# Power.net
KiCad netlist of a schematic drawn in Altium Designer
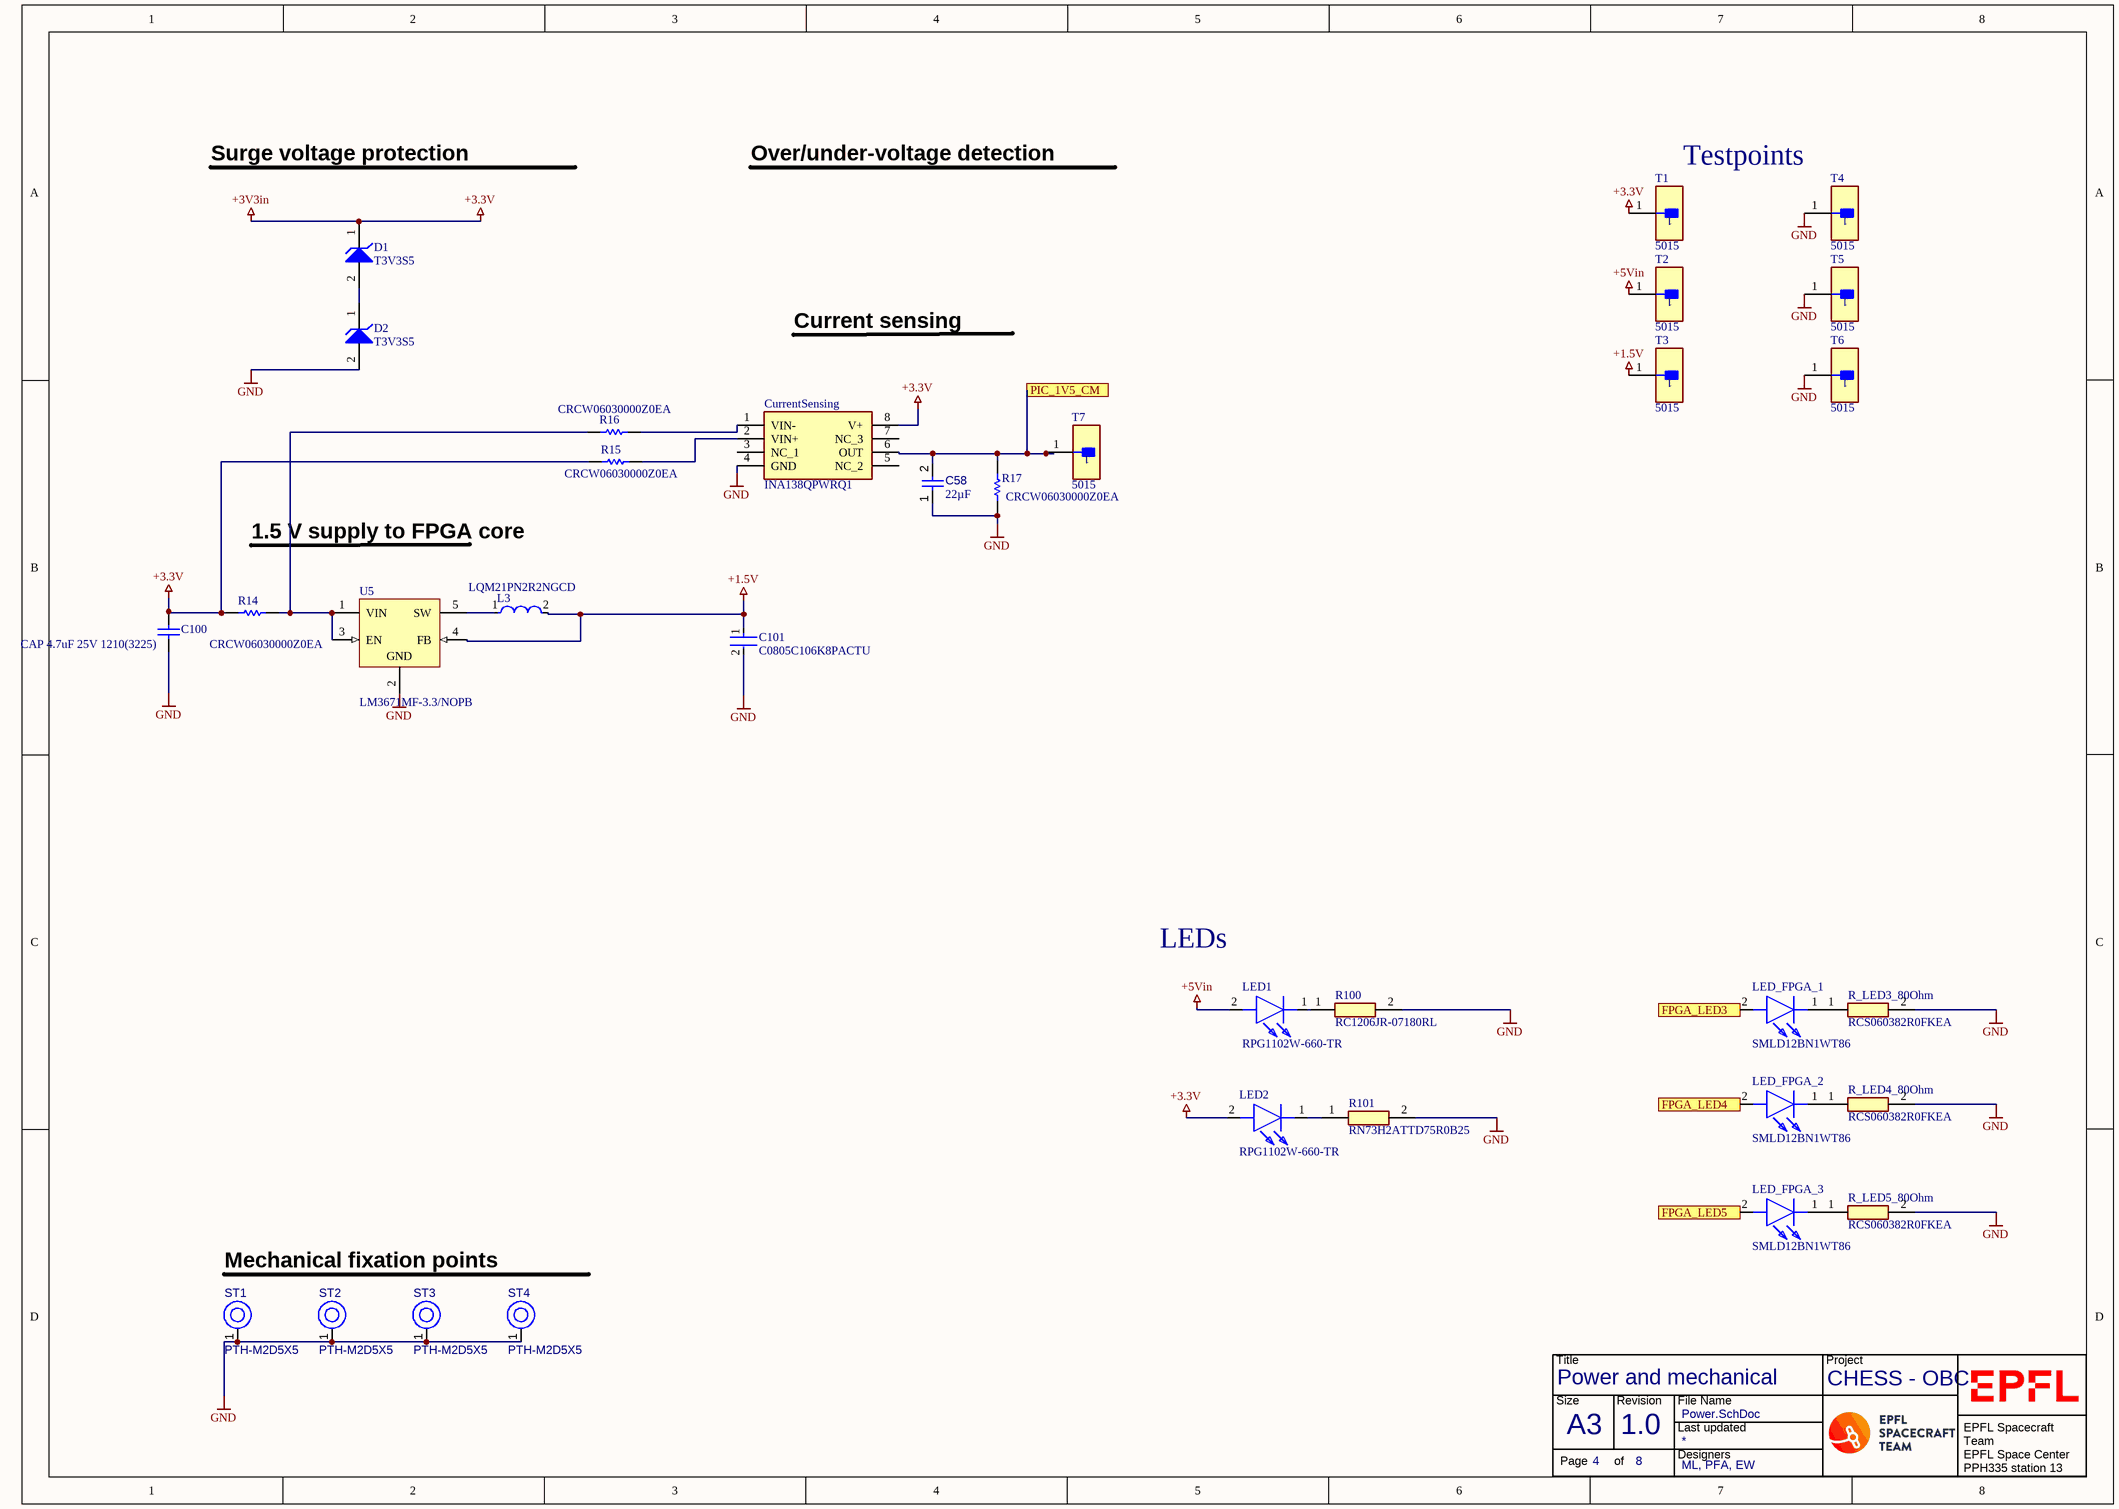
[diagram p0: Power.SchDoc]

(export (version "E")
  (design (tool "Eeschema 10.0.6"))
  (components
    (comp (ref "C58")
      (value "22µF")
      (footprint "CAPC0805(2012)145_L")
      (description "Chip Capacitor, 22µF +/-40%, 16V, 0805, Thickness 1.45 mm")
      (fields (field (name "TOLERANCE") "5%") (field (name "Comment") "Capacitor 22µF +/-40% 16V 0805"))
      (libsource (lib "EPFL") (part "CAP-NP-2"))
    )
    (comp (ref "C100")
      (value "CAP 4.7uF 25V 1210(3225)")
      (footprint "CAPC1210(3225)220_M")
      (description "CAP 4.7uF 25V ±10% 1210 (3225 Metric) Thickness 2.2mm SMD")
      (fields (field (name "TOLERANCE") "Â±10%"))
      (libsource (lib "Altium Content Vault") (part "CAP"))
    )
    (comp (ref "C101")
      (value "C0805C106K8PACTU")
      (footprint "FP-C0805C-DG-MFG")
      (description "CAP CER 10UF 10V X5R 0805")
      (fields (field (name "TOLERANCE") "10%") (field (name "MANUFACTURER") "Kemet"))
      (libsource (lib "Altium Content Vault") (part "11868f565c42a9108669ba33697ecf6"))
    )
    (comp (ref "CurrentSensing")
      (value "INA138QPWRQ1")
      (footprint "SamacSys:SOP65P640X120-8N")
      (description "Integrated Circuit")
      (fields (field (name "MOUSER2 PART NUMBER") "595-INA138QPWRQ1"))
      (libsource (lib "*") (part "INA138QPWRQ1"))
    )
    (comp (ref "D1")
      (value "T3V3S5")
      (footprint "ONSC-SOD-523-2-502-01_V")
      (fields (field (name "MANUFACTURER") "On Semiconductor") (field (name "PARTNUMBER") "ESD5Z7.0T1G"))
      (libsource (lib "Altium Content Vault") (part "ONSC-K1A2-2"))
    )
    (comp (ref "D2")
      (value "T3V3S5")
      (footprint "ONSC-SOD-523-2-502-01_V")
      (fields (field (name "MANUFACTURER") "On Semiconductor") (field (name "PARTNUMBER") "ESD5Z7.0T1G"))
      (libsource (lib "Altium Content Vault") (part "ONSC-K1A2-2"))
    )
    (comp (ref "L3")
      (value "LQM21PN2R2NGCD")
      (footprint "FP-LQM21PH_G0-IPC_C")
      (description "Multilayer Type Inductor for Power Lines, 0805 (2012), 2.2μH, 30%, 0.288Ω, 0.8A")
      (fields (field (name "TOLERANCE") "30%"))
      (libsource (lib "Altium Content Vault") (part "725321dda6339637d4d059423bc1c3c"))
    )
    (comp (ref "LED1")
      (value "RPG1102W-660-TR")
      (footprint "SamacSys:LEDC3015X190N")
      (description "LED")
      (fields (field (name "MOUSER2 PART NUMBER") "327-RPG1102W660TR"))
      (libsource (lib "*") (part "RPG1102W-660-TR"))
    )
    (comp (ref "LED2")
      (value "RPG1102W-660-TR")
      (footprint "SamacSys:LEDC3015X190N")
      (description "LED")
      (fields (field (name "MOUSER2 PART NUMBER") "327-RPG1102W660TR"))
      (libsource (lib "*") (part "RPG1102W-660-TR"))
    )
    (comp (ref "LED_FPGA_1")
      (value "SMLD12BN1WT86")
      (footprint "SamacSys:LEDM168X65N")
      (description "LED")
      (libsource (lib "*") (part "SMLD12BN1WT86"))
    )
    (comp (ref "LED_FPGA_2")
      (value "SMLD12BN1WT86")
      (footprint "SamacSys:LEDM168X65N")
      (description "LED")
      (libsource (lib "*") (part "SMLD12BN1WT86"))
    )
    (comp (ref "LED_FPGA_3")
      (value "SMLD12BN1WT86")
      (footprint "SamacSys:LEDM168X65N")
      (description "LED")
      (libsource (lib "*") (part "SMLD12BN1WT86"))
    )
    (comp (ref "R14")
      (value "CRCW06030000Z0EA")
      (footprint "RESC1609X50X30NL8T20")
      (description "Chip Resistor, 0 Ohm, Jumper, 100 mW, -55 to 155 degC, 0603 (1608 Metric), RoHS, Tape and Reel")
      (fields (field (name "MANUFACTURER") "Vishay Semiconductor"))
      (libsource (lib "Altium Content Vault") (part "RES-2"))
    )
    (comp (ref "R15")
      (value "CRCW06030000Z0EA")
      (footprint "RESC1609X50X30NL8T20")
      (description "Chip Resistor, 0 Ohm, Jumper, 100 mW, -55 to 155 degC, 0603 (1608 Metric), RoHS, Tape and Reel")
      (fields (field (name "MANUFACTURER") "Vishay Semiconductor"))
      (libsource (lib "Altium Content Vault") (part "RES-2"))
    )
    (comp (ref "R16")
      (value "CRCW06030000Z0EA")
      (footprint "RESC1609X50X30NL8T20")
      (description "Chip Resistor, 0 Ohm, Jumper, 100 mW, -55 to 155 degC, 0603 (1608 Metric), RoHS, Tape and Reel")
      (fields (field (name "MANUFACTURER") "Vishay Semiconductor"))
      (libsource (lib "Altium Content Vault") (part "RES-2"))
    )
    (comp (ref "R17")
      (value "CRCW06030000Z0EA")
      (footprint "RESC1609X50X30NL8T20")
      (description "Chip Resistor, 0 Ohm, Jumper, 100 mW, -55 to 155 degC, 0603 (1608 Metric), RoHS, Tape and Reel")
      (fields (field (name "MANUFACTURER") "Vishay Semiconductor"))
      (libsource (lib "Altium Content Vault") (part "RES-2"))
    )
    (comp (ref "R100")
      (value "RC1206JR-07180RL")
      (footprint "SamacSys:RESC3116X65N")
      (description "Resistor")
      (libsource (lib "*") (part "RC1206JR-07180RL"))
    )
    (comp (ref "R101")
      (value "RN73H2ATTD75R0B25")
      (footprint "SamacSys:RESC2012X60N")
      (description "Resistor")
      (libsource (lib "*") (part "RN73H2ATTD75R0B25"))
    )
    (comp (ref "R_LED3_80Ohm")
      (value "RCS060382R0FKEA")
      (footprint "SamacSys:RESC1608X50N")
      (description "Resistor")
      (fields (field (name "MOUSER2 PART NUMBER") "71-RCS060382R0FKEA"))
      (libsource (lib "*") (part "RCS060382R0FKEA"))
    )
    (comp (ref "R_LED4_80Ohm")
      (value "RCS060382R0FKEA")
      (footprint "SamacSys:RESC1608X50N")
      (description "Resistor")
      (fields (field (name "MOUSER2 PART NUMBER") "71-RCS060382R0FKEA"))
      (libsource (lib "*") (part "RCS060382R0FKEA"))
    )
    (comp (ref "R_LED5_80Ohm")
      (value "RCS060382R0FKEA")
      (footprint "SamacSys:RESC1608X50N")
      (description "Resistor")
      (fields (field (name "MOUSER2 PART NUMBER") "71-RCS060382R0FKEA"))
      (libsource (lib "*") (part "RCS060382R0FKEA"))
    )
    (comp (ref "ST1")
      (value "PTH-M2D5X5")
      (footprint "PTH-M2D5X5")
      (description "M2 PTH (2.5mm), 5mm pad")
      (libsource (lib "EPFL") (part "CMP-00028-00000-1"))
    )
    (comp (ref "ST2")
      (value "PTH-M2D5X5")
      (footprint "PTH-M2D5X5")
      (description "M2 PTH (2.5mm), 5mm pad")
      (libsource (lib "EPFL") (part "CMP-00028-00000-1"))
    )
    (comp (ref "ST3")
      (value "PTH-M2D5X5")
      (footprint "PTH-M2D5X5")
      (description "M2 PTH (2.5mm), 5mm pad")
      (libsource (lib "EPFL") (part "CMP-00028-00000-1"))
    )
    (comp (ref "ST4")
      (value "PTH-M2D5X5")
      (footprint "PTH-M2D5X5")
      (description "M2 PTH (2.5mm), 5mm pad")
      (libsource (lib "EPFL") (part "CMP-00028-00000-1"))
    )
    (comp (ref "T1")
      (value "5015")
      (footprint "FP-5015-MFG")
      (description "PC TEST POINT MINIATURE")
      (fields
        (field (name "MANUFACTURER") "keystone")
        (field (name "OCTOPART") "https://octopart.com/5015-keystone-3822")
      )
      (libsource (lib "Altium Content Vault") (part "dd45045ce8184df9e99e12baf3f412c"))
    )
    (comp (ref "T2")
      (value "5015")
      (footprint "FP-5015-MFG")
      (description "PC TEST POINT MINIATURE")
      (fields
        (field (name "MANUFACTURER") "keystone")
        (field (name "OCTOPART") "https://octopart.com/5015-keystone-3822")
      )
      (libsource (lib "Altium Content Vault") (part "dd45045ce8184df9e99e12baf3f412c"))
    )
    (comp (ref "T3")
      (value "5015")
      (footprint "FP-5015-MFG")
      (description "PC TEST POINT MINIATURE")
      (fields
        (field (name "MANUFACTURER") "keystone")
        (field (name "OCTOPART") "https://octopart.com/5015-keystone-3822")
      )
      (libsource (lib "Altium Content Vault") (part "dd45045ce8184df9e99e12baf3f412c"))
    )
    (comp (ref "T4")
      (value "5015")
      (footprint "FP-5015-MFG")
      (description "PC TEST POINT MINIATURE")
      (fields
        (field (name "MANUFACTURER") "keystone")
        (field (name "OCTOPART") "https://octopart.com/5015-keystone-3822")
      )
      (libsource (lib "Altium Content Vault") (part "dd45045ce8184df9e99e12baf3f412c"))
    )
    (comp (ref "T5")
      (value "5015")
      (footprint "FP-5015-MFG")
      (description "PC TEST POINT MINIATURE")
      (fields
        (field (name "MANUFACTURER") "keystone")
        (field (name "OCTOPART") "https://octopart.com/5015-keystone-3822")
      )
      (libsource (lib "Altium Content Vault") (part "dd45045ce8184df9e99e12baf3f412c"))
    )
    (comp (ref "T6")
      (value "5015")
      (footprint "FP-5015-MFG")
      (description "PC TEST POINT MINIATURE")
      (fields
        (field (name "MANUFACTURER") "keystone")
        (field (name "OCTOPART") "https://octopart.com/5015-keystone-3822")
      )
      (libsource (lib "Altium Content Vault") (part "dd45045ce8184df9e99e12baf3f412c"))
    )
    (comp (ref "T7")
      (value "5015")
      (footprint "FP-5015-MFG")
      (description "PC TEST POINT MINIATURE")
      (fields
        (field (name "MANUFACTURER") "keystone")
        (field (name "OCTOPART") "https://octopart.com/5015-keystone-3822")
      )
      (libsource (lib "Altium Content Vault") (part "dd45045ce8184df9e99e12baf3f412c"))
    )
    (comp (ref "U5")
      (value "LM3671MF-3.3/NOPB")
      (footprint "DBV0005A_N")
      (description "2MHz, 600mA Step-Down DC-DC Converter, 5-pin SOT-23, Pb-Free")
      (fields (field (name "MANUFACTURER") "Texas Instruments"))
      (libsource (lib "Altium Content Vault") (part "PM-DCDC-LM3670-5"))
    )
  )
  (nets
    (net (code "1") (name "+1.5V") (class "Default")
      (node (ref "C101") (pin "1") (pinfunction "1_1") (pintype "passive"))
      (node (ref "L3") (pin "2") (pinfunction "2_2") (pintype "passive"))
      (node (ref "T3") (pin "1") (pinfunction "1_1") (pintype "passive"))
      (node (ref "U5") (pin "4") (pinfunction "FB_4") (pintype "input"))
    )
    (net (code "2") (name "+3.3V") (class "Default")
      (node (ref "C100") (pin "2") (pinfunction "2_2") (pintype "passive"))
      (node (ref "CurrentSensing") (pin "8") (pinfunction "V+_8") (pintype "passive"))
      (node (ref "D1") (pin "1") (pinfunction "K_1") (pintype "passive"))
      (node (ref "LED2") (pin "2") (pinfunction "A_2") (pintype "passive"))
      (node (ref "R14") (pin "1") (pinfunction "1_1") (pintype "passive"))
      (node (ref "R15") (pin "1") (pinfunction "1_1") (pintype "passive"))
      (node (ref "T1") (pin "1") (pinfunction "1_1") (pintype "passive"))
    )
    (net (code "3") (name "+5Vin") (class "Default")
      (node (ref "LED1") (pin "2") (pinfunction "A_2") (pintype "passive"))
      (node (ref "T2") (pin "1") (pinfunction "1_1") (pintype "passive"))
    )
    (net (code "4") (name "/FPGA_LED3") (class "Default")
      (node (ref "LED_FPGA_1") (pin "2") (pinfunction "A_2") (pintype "passive"))
    )
    (net (code "5") (name "/FPGA_LED4") (class "Default")
      (node (ref "LED_FPGA_2") (pin "2") (pinfunction "A_2") (pintype "passive"))
    )
    (net (code "6") (name "/FPGA_LED5") (class "Default")
      (node (ref "LED_FPGA_3") (pin "2") (pinfunction "A_2") (pintype "passive"))
    )
    (net (code "7") (name "/PIC_1V5_CM") (class "Default")
      (node (ref "C58") (pin "2") (pinfunction "2_2") (pintype "passive"))
      (node (ref "CurrentSensing") (pin "6") (pinfunction "OUT_6") (pintype "passive"))
      (node (ref "R17") (pin "2") (pinfunction "2_2") (pintype "passive"))
      (node (ref "T7") (pin "1") (pinfunction "1_1") (pintype "passive"))
    )
    (net (code "8") (name "GND") (class "Default")
      (node (ref "C100") (pin "1") (pinfunction "1_1") (pintype "passive"))
      (node (ref "C101") (pin "2") (pinfunction "2_2") (pintype "passive"))
      (node (ref "C58") (pin "1") (pinfunction "1_1") (pintype "passive"))
      (node (ref "CurrentSensing") (pin "4") (pinfunction "GND_4") (pintype "passive"))
      (node (ref "D2") (pin "2") (pinfunction "A_2") (pintype "passive"))
      (node (ref "R100") (pin "2") (pinfunction "2_2") (pintype "passive"))
      (node (ref "R101") (pin "2") (pinfunction "2_2") (pintype "passive"))
      (node (ref "R17") (pin "1") (pinfunction "1_1") (pintype "passive"))
      (node (ref "R_LED3_80Ohm") (pin "2") (pinfunction "2_2") (pintype "passive"))
      (node (ref "R_LED4_80Ohm") (pin "2") (pinfunction "2_2") (pintype "passive"))
      (node (ref "R_LED5_80Ohm") (pin "2") (pinfunction "2_2") (pintype "passive"))
      (node (ref "ST1") (pin "1") (pinfunction "H1_1") (pintype "passive"))
      (node (ref "ST2") (pin "1") (pinfunction "H1_1") (pintype "passive"))
      (node (ref "ST3") (pin "1") (pinfunction "H1_1") (pintype "passive"))
      (node (ref "ST4") (pin "1") (pinfunction "H1_1") (pintype "passive"))
      (node (ref "T4") (pin "1") (pinfunction "1_1") (pintype "passive"))
      (node (ref "T5") (pin "1") (pinfunction "1_1") (pintype "passive"))
      (node (ref "T6") (pin "1") (pinfunction "1_1") (pintype "passive"))
      (node (ref "U5") (pin "2") (pinfunction "GND_2") (pintype "power_in"))
    )
    (net (code "9") (name "Net-(CurrentSensing-VIN+)") (class "Default")
      (node (ref "CurrentSensing") (pin "2") (pinfunction "VIN+_2") (pintype "passive"))
      (node (ref "R15") (pin "2") (pinfunction "2_2") (pintype "passive"))
    )
    (net (code "10") (name "Net-(CurrentSensing-VIN-)") (class "Default")
      (node (ref "CurrentSensing") (pin "1") (pinfunction "VIN-_1") (pintype "passive"))
      (node (ref "R16") (pin "2") (pinfunction "2_2") (pintype "passive"))
    )
    (net (code "11") (name "Net-(D1-A)") (class "Default")
      (node (ref "D1") (pin "2") (pinfunction "A_2") (pintype "passive"))
      (node (ref "D2") (pin "1") (pinfunction "K_1") (pintype "passive"))
    )
    (net (code "12") (name "Net-(LED1-K)") (class "Default")
      (node (ref "LED1") (pin "1") (pinfunction "K_1") (pintype "passive"))
      (node (ref "R100") (pin "1") (pinfunction "1_1") (pintype "passive"))
    )
    (net (code "13") (name "Net-(LED2-K)") (class "Default")
      (node (ref "LED2") (pin "1") (pinfunction "K_1") (pintype "passive"))
      (node (ref "R101") (pin "1") (pinfunction "1_1") (pintype "passive"))
    )
    (net (code "14") (name "Net-(LED_FPGA_1-K)") (class "Default")
      (node (ref "LED_FPGA_1") (pin "1") (pinfunction "K_1") (pintype "passive"))
      (node (ref "R_LED3_80Ohm") (pin "1") (pinfunction "1_1") (pintype "passive"))
    )
    (net (code "15") (name "Net-(LED_FPGA_2-K)") (class "Default")
      (node (ref "LED_FPGA_2") (pin "1") (pinfunction "K_1") (pintype "passive"))
      (node (ref "R_LED4_80Ohm") (pin "1") (pinfunction "1_1") (pintype "passive"))
    )
    (net (code "16") (name "Net-(LED_FPGA_3-K)") (class "Default")
      (node (ref "LED_FPGA_3") (pin "1") (pinfunction "K_1") (pintype "passive"))
      (node (ref "R_LED5_80Ohm") (pin "1") (pinfunction "1_1") (pintype "passive"))
    )
    (net (code "17") (name "Net-(U5-EN)") (class "Default")
      (node (ref "R14") (pin "2") (pinfunction "2_2") (pintype "passive"))
      (node (ref "R16") (pin "1") (pinfunction "1_1") (pintype "passive"))
      (node (ref "U5") (pin "1") (pinfunction "VIN_1") (pintype "power_in"))
      (node (ref "U5") (pin "3") (pinfunction "EN_3") (pintype "input"))
    )
    (net (code "18") (name "Net-(U5-SW)") (class "Default")
      (node (ref "L3") (pin "1") (pinfunction "1_1") (pintype "passive"))
      (node (ref "U5") (pin "5") (pinfunction "SW_5") (pintype "power_in"))
    )
    (net (code "19") (name "unconnected-(CurrentSensing-NC_1-Pad3)") (class "Default")
      (node (ref "CurrentSensing") (pin "3") (pinfunction "NC_1_3") (pintype "passive"))
    )
    (net (code "20") (name "unconnected-(CurrentSensing-NC_2-Pad5)") (class "Default")
      (node (ref "CurrentSensing") (pin "5") (pinfunction "NC_2_5") (pintype "passive"))
    )
    (net (code "21") (name "unconnected-(CurrentSensing-NC_3-Pad7)") (class "Default")
      (node (ref "CurrentSensing") (pin "7") (pinfunction "NC_3_7") (pintype "passive"))
    )
  )
)
